# atxmega_e5_1.net
KiCad netlist of a schematic drawn in EAGLE
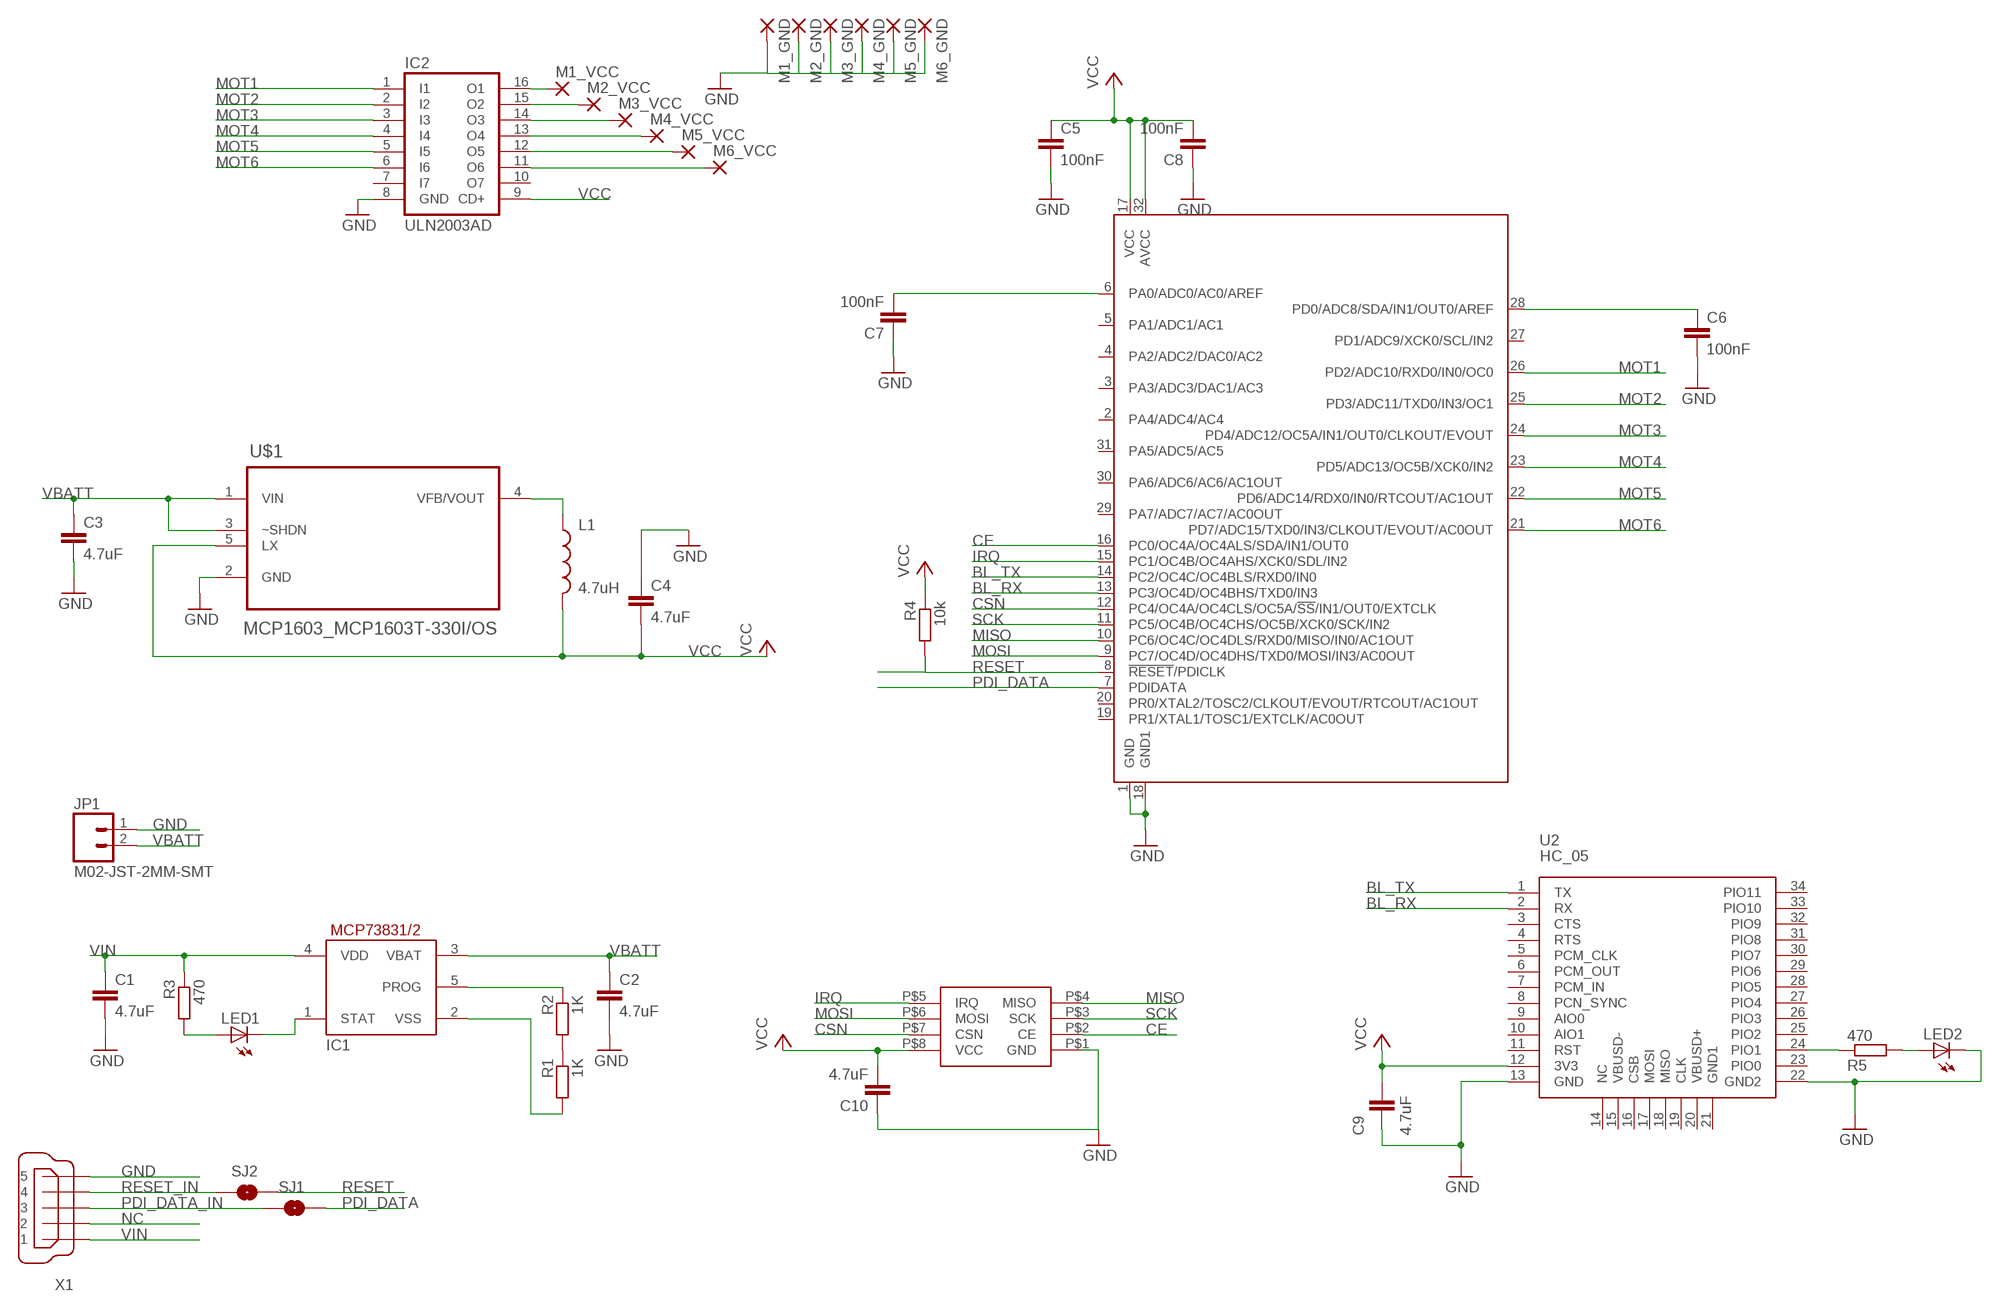
[diagram p0: schematic, sheet 1]

(export (version "E")
  (design (tool "Eeschema 10.0.6"))
  (components
    (comp (ref "C1")
      (value "4.7uF")
      (footprint "eagle-import:C0603K")
      (libsource (lib "eagle-import") (part "C-EUC0603K"))
    )
    (comp (ref "C2")
      (value "4.7uF")
      (footprint "eagle-import:C0603K")
      (libsource (lib "eagle-import") (part "C-EUC0603K"))
    )
    (comp (ref "C3")
      (value "4.7uF")
      (footprint "eagle-import:C0603K")
      (libsource (lib "eagle-import") (part "C-EUC0603K"))
    )
    (comp (ref "C4")
      (value "4.7uF")
      (footprint "eagle-import:C0603K")
      (libsource (lib "eagle-import") (part "C-EUC0603K"))
    )
    (comp (ref "C5")
      (value "100nF")
      (footprint "eagle-import:C0603K")
      (libsource (lib "eagle-import") (part "C-EUC0603K"))
    )
    (comp (ref "C6")
      (value "100nF")
      (footprint "eagle-import:C0603K")
      (libsource (lib "eagle-import") (part "C-EUC0603K"))
    )
    (comp (ref "C7")
      (value "100nF")
      (footprint "eagle-import:C0603K")
      (libsource (lib "eagle-import") (part "C-EUC0603K"))
    )
    (comp (ref "C8")
      (value "100nF")
      (footprint "eagle-import:C0603K")
      (libsource (lib "eagle-import") (part "C-EUC0603K"))
    )
    (comp (ref "C9")
      (value "4.7uF")
      (footprint "eagle-import:C0603K")
      (libsource (lib "eagle-import") (part "C-EUC0603K"))
    )
    (comp (ref "C10")
      (value "4.7uF")
      (footprint "eagle-import:C0603K")
      (libsource (lib "eagle-import") (part "C-EUC0603K"))
    )
    (comp (ref "IC1")
      (value "MCP73831/OT")
      (footprint "eagle-import:SOT23-5L")
      (libsource (lib "eagle-import") (part "MCP73831/OT"))
    )
    (comp (ref "IC2")
      (value "ULN2003AD")
      (footprint "eagle-import:SO16")
      (libsource (lib "eagle-import") (part "ULN2003AD"))
    )
    (comp (ref "JP1")
      (value "M02-JST-2MM-SMT")
      (footprint "eagle-import:JST-2-SMD")
      (libsource (lib "eagle-import") (part "M02-JST-2MM-SMT"))
    )
    (comp (ref "L1")
      (value "4.7uH")
      (footprint "eagle-import:1007")
      (libsource (lib "eagle-import") (part "INDUCTOR1007"))
    )
    (comp (ref "LED1")
      (value "LED0805LED")
      (footprint "eagle-import:0805LED")
      (libsource (lib "eagle-import") (part "LED0805LED"))
    )
    (comp (ref "LED2")
      (value "LED0805LED")
      (footprint "eagle-import:0805LED")
      (libsource (lib "eagle-import") (part "LED0805LED"))
    )
    (comp (ref "M1_GND")
      (value "WIREPAD2,15/1,0")
      (footprint "eagle-import:2,15_1,0")
      (libsource (lib "eagle-import") (part "WIREPAD2,15/1,0"))
    )
    (comp (ref "M1_VCC")
      (value "WIREPAD2,15/1,0")
      (footprint "eagle-import:2,15_1,0")
      (libsource (lib "eagle-import") (part "WIREPAD2,15/1,0"))
    )
    (comp (ref "M2_GND")
      (value "WIREPAD2,15/1,0")
      (footprint "eagle-import:2,15_1,0")
      (libsource (lib "eagle-import") (part "WIREPAD2,15/1,0"))
    )
    (comp (ref "M2_VCC")
      (value "WIREPAD2,15/1,0")
      (footprint "eagle-import:2,15_1,0")
      (libsource (lib "eagle-import") (part "WIREPAD2,15/1,0"))
    )
    (comp (ref "M3_GND")
      (value "WIREPAD2,15/1,0")
      (footprint "eagle-import:2,15_1,0")
      (libsource (lib "eagle-import") (part "WIREPAD2,15/1,0"))
    )
    (comp (ref "M3_VCC")
      (value "WIREPAD2,15/1,0")
      (footprint "eagle-import:2,15_1,0")
      (libsource (lib "eagle-import") (part "WIREPAD2,15/1,0"))
    )
    (comp (ref "M4_GND")
      (value "WIREPAD2,15/1,0")
      (footprint "eagle-import:2,15_1,0")
      (libsource (lib "eagle-import") (part "WIREPAD2,15/1,0"))
    )
    (comp (ref "M4_VCC")
      (value "WIREPAD2,15/1,0")
      (footprint "eagle-import:2,15_1,0")
      (libsource (lib "eagle-import") (part "WIREPAD2,15/1,0"))
    )
    (comp (ref "M5_GND")
      (value "WIREPAD2,15/1,0")
      (footprint "eagle-import:2,15_1,0")
      (libsource (lib "eagle-import") (part "WIREPAD2,15/1,0"))
    )
    (comp (ref "M5_VCC")
      (value "WIREPAD2,15/1,0")
      (footprint "eagle-import:2,15_1,0")
      (libsource (lib "eagle-import") (part "WIREPAD2,15/1,0"))
    )
    (comp (ref "M6_GND")
      (value "WIREPAD2,15/1,0")
      (footprint "eagle-import:2,15_1,0")
      (libsource (lib "eagle-import") (part "WIREPAD2,15/1,0"))
    )
    (comp (ref "M6_VCC")
      (value "WIREPAD2,15/1,0")
      (footprint "eagle-import:2,15_1,0")
      (libsource (lib "eagle-import") (part "WIREPAD2,15/1,0"))
    )
    (comp (ref "R1")
      (value "1K")
      (footprint "eagle-import:R0603")
      (libsource (lib "eagle-import") (part "R-EU_R0603"))
    )
    (comp (ref "R2")
      (value "1K")
      (footprint "eagle-import:R0603")
      (libsource (lib "eagle-import") (part "R-EU_R0603"))
    )
    (comp (ref "R3")
      (value "470")
      (footprint "eagle-import:R0603")
      (libsource (lib "eagle-import") (part "R-EU_R0603"))
    )
    (comp (ref "R4")
      (value "10k")
      (footprint "eagle-import:R0603")
      (libsource (lib "eagle-import") (part "R-EU_R0603"))
    )
    (comp (ref "R5")
      (value "470")
      (footprint "eagle-import:R0603")
      (libsource (lib "eagle-import") (part "R-EU_R0603"))
    )
    (comp (ref "SJ1")
      (value "SOLDERJUMPERNO")
      (footprint "eagle-import:SJ_2S-NO")
      (libsource (lib "eagle-import") (part "SOLDERJUMPERNO"))
    )
    (comp (ref "SJ2")
      (value "SOLDERJUMPERNO")
      (footprint "eagle-import:SJ_2S-NO")
      (libsource (lib "eagle-import") (part "SOLDERJUMPERNO"))
    )
    (comp (ref "U$1")
      (value "MCP1603_MCP1603T-330I/OS")
      (footprint "eagle-import:MCP1603_SOT95P280X110-5N")
      (fields (field (name "MPN") "MCP1603T-330I/OS"))
      (libsource (lib "eagle-import") (part "MCP1603_MCP1603T-330I/OS"))
    )
    (comp (ref "U$2")
      (value "NRF24L01+")
      (footprint "eagle-import:NRF24L01+")
      (libsource (lib "eagle-import") (part "NRF24L01+"))
    )
    (comp (ref "U1")
      (value "ATXMEGAE5AU")
      (footprint "eagle-import:TQFP32")
      (libsource (lib "eagle-import") (part "ATXMEGAE5AU"))
    )
    (comp (ref "U2")
      (value "HC_05")
      (footprint "eagle-import:BLUETOOTH_SMD")
      (libsource (lib "eagle-import") (part "HC_05"))
    )
    (comp (ref "X1")
      (value "MINI-USB-32005-201")
      (footprint "eagle-import:32005-201")
      (libsource (lib "eagle-import") (part "MINI-USB-32005-201"))
    )
  )
  (nets
    (net (code "1") (name "/BL_RX") (class "Default")
      (node (ref "U1") (pin "13") (pinfunction "PC3/OC4D/OC4BHS/TXD0/IN3_13") (pintype "bidirectional"))
      (node (ref "U2") (pin "2") (pinfunction "RX_2") (pintype "bidirectional"))
    )
    (net (code "2") (name "/BL_TX") (class "Default")
      (node (ref "U1") (pin "14") (pinfunction "PC2/OC4C/OC4BLS/RXD0/IN0_14") (pintype "bidirectional"))
      (node (ref "U2") (pin "1") (pinfunction "TX_1") (pintype "bidirectional"))
    )
    (net (code "3") (name "/CE") (class "Default")
      (node (ref "U$2") (pin "P$2") (pinfunction "CE_P$2") (pintype "bidirectional"))
      (node (ref "U1") (pin "16") (pinfunction "PC0/OC4A/OC4ALS/SDA/IN1/OUT0_16") (pintype "bidirectional"))
    )
    (net (code "4") (name "/CSN") (class "Default")
      (node (ref "U$2") (pin "P$7") (pinfunction "CSN_P$7") (pintype "bidirectional"))
      (node (ref "U1") (pin "12") (pinfunction "PC4/OC4A/OC4CLS/OC5A/~{SS}/IN1/OUT0/EXTCLK_12") (pintype "bidirectional"))
    )
    (net (code "5") (name "/IRQ") (class "Default")
      (node (ref "U$2") (pin "P$5") (pinfunction "IRQ_P$5") (pintype "bidirectional"))
      (node (ref "U1") (pin "15") (pinfunction "PC1/OC4B/OC4AHS/XCK0/SDL/IN2_15") (pintype "bidirectional"))
    )
    (net (code "6") (name "/MISO") (class "Default")
      (node (ref "U$2") (pin "P$4") (pinfunction "MISO_P$4") (pintype "bidirectional"))
      (node (ref "U1") (pin "10") (pinfunction "PC6/OC4C/OC4DLS/RXD0/MISO/IN0/AC1OUT_10") (pintype "bidirectional"))
    )
    (net (code "7") (name "/MOSI") (class "Default")
      (node (ref "U$2") (pin "P$6") (pinfunction "MOSI_P$6") (pintype "bidirectional"))
      (node (ref "U1") (pin "9") (pinfunction "PC7/OC4D/OC4DHS/TXD0/MOSI/IN3/AC0OUT_9") (pintype "bidirectional"))
    )
    (net (code "8") (name "/MOT1") (class "Default")
      (node (ref "IC2") (pin "1") (pinfunction "I1_1") (pintype "input"))
      (node (ref "U1") (pin "26") (pinfunction "PD2/ADC10/RXD0/IN0/OC0_26") (pintype "bidirectional"))
    )
    (net (code "9") (name "/MOT2") (class "Default")
      (node (ref "IC2") (pin "2") (pinfunction "I2_2") (pintype "input"))
      (node (ref "U1") (pin "25") (pinfunction "PD3/ADC11/TXD0/IN3/OC1_25") (pintype "bidirectional"))
    )
    (net (code "10") (name "/MOT3") (class "Default")
      (node (ref "IC2") (pin "3") (pinfunction "I3_3") (pintype "input"))
      (node (ref "U1") (pin "24") (pinfunction "PD4/ADC12/OC5A/IN1/OUT0/CLKOUT/EVOUT_24") (pintype "bidirectional"))
    )
    (net (code "11") (name "/MOT4") (class "Default")
      (node (ref "IC2") (pin "4") (pinfunction "I4_4") (pintype "input"))
      (node (ref "U1") (pin "23") (pinfunction "PD5/ADC13/OC5B/XCK0/IN2_23") (pintype "bidirectional"))
    )
    (net (code "12") (name "/MOT5") (class "Default")
      (node (ref "IC2") (pin "5") (pinfunction "I5_5") (pintype "input"))
      (node (ref "U1") (pin "22") (pinfunction "PD6/ADC14/RDX0/IN0/RTCOUT/AC1OUT_22") (pintype "bidirectional"))
    )
    (net (code "13") (name "/MOT6") (class "Default")
      (node (ref "IC2") (pin "6") (pinfunction "I6_6") (pintype "input"))
      (node (ref "U1") (pin "21") (pinfunction "PD7/ADC15/TXD0/IN3/CLKOUT/EVOUT/AC0OUT_21") (pintype "bidirectional"))
    )
    (net (code "14") (name "/NC") (class "Default")
      (node (ref "X1") (pin "2") (pinfunction "2_2") (pintype "passive"))
    )
    (net (code "15") (name "/PDI_DATA") (class "Default")
      (node (ref "SJ1") (pin "2") (pinfunction "2_2") (pintype "passive"))
      (node (ref "U1") (pin "7") (pinfunction "PDIDATA_7") (pintype "bidirectional"))
    )
    (net (code "16") (name "/PDI_DATA_IN") (class "Default")
      (node (ref "SJ1") (pin "1") (pinfunction "1_1") (pintype "passive"))
      (node (ref "X1") (pin "3") (pinfunction "3_3") (pintype "passive"))
    )
    (net (code "17") (name "/RESET") (class "Default")
      (node (ref "R4") (pin "2") (pinfunction "2_2") (pintype "passive"))
      (node (ref "SJ2") (pin "2") (pinfunction "2_2") (pintype "passive"))
      (node (ref "U1") (pin "8") (pinfunction "~{RESET}/PDICLK_8") (pintype "bidirectional"))
    )
    (net (code "18") (name "/RESET_IN") (class "Default")
      (node (ref "SJ2") (pin "1") (pinfunction "1_1") (pintype "passive"))
      (node (ref "X1") (pin "4") (pinfunction "4_4") (pintype "passive"))
    )
    (net (code "19") (name "/SCK") (class "Default")
      (node (ref "U$2") (pin "P$3") (pinfunction "SCK_P$3") (pintype "bidirectional"))
      (node (ref "U1") (pin "11") (pinfunction "PC5/OC4B/OC4CHS/OC5B/XCK0/SCK/IN2_11") (pintype "bidirectional"))
    )
    (net (code "20") (name "/VBATT") (class "Default")
      (node (ref "C2") (pin "1") (pinfunction "1_1") (pintype "passive"))
      (node (ref "C3") (pin "1") (pinfunction "1_1") (pintype "passive"))
      (node (ref "IC1") (pin "3") (pinfunction "VBAT_3") (pintype "bidirectional"))
      (node (ref "JP1") (pin "2") (pinfunction "1_2") (pintype "passive"))
      (node (ref "U$1") (pin "1") (pinfunction "VIN_1") (pintype "power_in"))
      (node (ref "U$1") (pin "3") (pinfunction "~{SHDN}_3") (pintype "input"))
    )
    (net (code "21") (name "/VIN") (class "Default")
      (node (ref "C1") (pin "1") (pinfunction "1_1") (pintype "passive"))
      (node (ref "IC1") (pin "4") (pinfunction "VDD_4") (pintype "power_in"))
      (node (ref "R3") (pin "1") (pinfunction "1_1") (pintype "passive"))
      (node (ref "X1") (pin "1") (pinfunction "1_1") (pintype "passive"))
    )
    (net (code "22") (name "GND") (class "Default")
      (node (ref "C1") (pin "2") (pinfunction "2_2") (pintype "passive"))
      (node (ref "C10") (pin "1") (pinfunction "1_1") (pintype "passive"))
      (node (ref "C2") (pin "2") (pinfunction "2_2") (pintype "passive"))
      (node (ref "C3") (pin "2") (pinfunction "2_2") (pintype "passive"))
      (node (ref "C4") (pin "1") (pinfunction "1_1") (pintype "passive"))
      (node (ref "C5") (pin "2") (pinfunction "2_2") (pintype "passive"))
      (node (ref "C6") (pin "2") (pinfunction "2_2") (pintype "passive"))
      (node (ref "C7") (pin "1") (pinfunction "1_1") (pintype "passive"))
      (node (ref "C8") (pin "1") (pinfunction "1_1") (pintype "passive"))
      (node (ref "C9") (pin "2") (pinfunction "2_2") (pintype "passive"))
      (node (ref "IC2") (pin "8") (pinfunction "GND_8") (pintype "power_in"))
      (node (ref "JP1") (pin "1") (pinfunction "2_1") (pintype "passive"))
      (node (ref "LED2") (pin "C") (pinfunction "C_C") (pintype "passive"))
      (node (ref "M1_GND") (pin "1") (pinfunction "P_1") (pintype "passive"))
      (node (ref "M2_GND") (pin "1") (pinfunction "P_1") (pintype "passive"))
      (node (ref "M3_GND") (pin "1") (pinfunction "P_1") (pintype "passive"))
      (node (ref "M4_GND") (pin "1") (pinfunction "P_1") (pintype "passive"))
      (node (ref "M5_GND") (pin "1") (pinfunction "P_1") (pintype "passive"))
      (node (ref "M6_GND") (pin "1") (pinfunction "P_1") (pintype "passive"))
      (node (ref "U$1") (pin "2") (pinfunction "GND_2") (pintype "passive"))
      (node (ref "U$2") (pin "P$1") (pinfunction "GND_P$1") (pintype "power_in"))
      (node (ref "U1") (pin "1") (pinfunction "GND_1") (pintype "bidirectional"))
      (node (ref "U1") (pin "18") (pinfunction "GND1_18") (pintype "bidirectional"))
      (node (ref "U2") (pin "13") (pinfunction "GND_13") (pintype "bidirectional"))
      (node (ref "U2") (pin "22") (pinfunction "GND2_22") (pintype "bidirectional"))
      (node (ref "X1") (pin "5") (pinfunction "5_5") (pintype "passive"))
    )
    (net (code "23") (name "Net-(IC1-PROG)") (class "Default")
      (node (ref "IC1") (pin "5") (pinfunction "PROG_5") (pintype "input"))
      (node (ref "R2") (pin "1") (pinfunction "1_1") (pintype "passive"))
    )
    (net (code "24") (name "Net-(IC1-STAT)") (class "Default")
      (node (ref "IC1") (pin "1") (pinfunction "STAT_1") (pintype "output"))
      (node (ref "LED1") (pin "C") (pinfunction "C_C") (pintype "passive"))
    )
    (net (code "25") (name "Net-(IC1-VSS)") (class "Default")
      (node (ref "IC1") (pin "2") (pinfunction "VSS_2") (pintype "power_in"))
      (node (ref "R1") (pin "2") (pinfunction "2_2") (pintype "passive"))
    )
    (net (code "26") (name "Net-(IC2-O1)") (class "Default")
      (node (ref "IC2") (pin "16") (pinfunction "O1_16") (pintype "open_collector"))
      (node (ref "M1_VCC") (pin "1") (pinfunction "P_1") (pintype "passive"))
    )
    (net (code "27") (name "Net-(IC2-O2)") (class "Default")
      (node (ref "IC2") (pin "15") (pinfunction "O2_15") (pintype "open_collector"))
      (node (ref "M2_VCC") (pin "1") (pinfunction "P_1") (pintype "passive"))
    )
    (net (code "28") (name "Net-(IC2-O3)") (class "Default")
      (node (ref "IC2") (pin "14") (pinfunction "O3_14") (pintype "open_collector"))
      (node (ref "M3_VCC") (pin "1") (pinfunction "P_1") (pintype "passive"))
    )
    (net (code "29") (name "Net-(IC2-O4)") (class "Default")
      (node (ref "IC2") (pin "13") (pinfunction "O4_13") (pintype "open_collector"))
      (node (ref "M4_VCC") (pin "1") (pinfunction "P_1") (pintype "passive"))
    )
    (net (code "30") (name "Net-(IC2-O5)") (class "Default")
      (node (ref "IC2") (pin "12") (pinfunction "O5_12") (pintype "open_collector"))
      (node (ref "M5_VCC") (pin "1") (pinfunction "P_1") (pintype "passive"))
    )
    (net (code "31") (name "Net-(IC2-O6)") (class "Default")
      (node (ref "IC2") (pin "11") (pinfunction "O6_11") (pintype "open_collector"))
      (node (ref "M6_VCC") (pin "1") (pinfunction "P_1") (pintype "passive"))
    )
    (net (code "32") (name "Net-(LED1-PadA)") (class "Default")
      (node (ref "LED1") (pin "A") (pinfunction "A_A") (pintype "passive"))
      (node (ref "R3") (pin "2") (pinfunction "2_2") (pintype "passive"))
    )
    (net (code "33") (name "Net-(LED2-PadA)") (class "Default")
      (node (ref "LED2") (pin "A") (pinfunction "A_A") (pintype "passive"))
      (node (ref "R5") (pin "2") (pinfunction "2_2") (pintype "passive"))
    )
    (net (code "34") (name "Net-(R1-Pad1)") (class "Default")
      (node (ref "R1") (pin "1") (pinfunction "1_1") (pintype "passive"))
      (node (ref "R2") (pin "2") (pinfunction "2_2") (pintype "passive"))
    )
    (net (code "35") (name "Net-(U$1-VFB{slash}VOUT)") (class "Default")
      (node (ref "L1") (pin "1") (pinfunction "1_1") (pintype "passive"))
      (node (ref "U$1") (pin "4") (pinfunction "VFB/VOUT_4") (pintype "output"))
    )
    (net (code "36") (name "Net-(U1-PA0{slash}ADC0{slash}AC0{slash}AREF)") (class "Default")
      (node (ref "C7") (pin "2") (pinfunction "2_2") (pintype "passive"))
      (node (ref "U1") (pin "6") (pinfunction "PA0/ADC0/AC0/AREF_6") (pintype "bidirectional"))
    )
    (net (code "37") (name "Net-(U1-PD0{slash}ADC8{slash}SDA{slash}IN1{slash}OUT0{slash}AREF)") (class "Default")
      (node (ref "C6") (pin "1") (pinfunction "1_1") (pintype "passive"))
      (node (ref "U1") (pin "28") (pinfunction "PD0/ADC8/SDA/IN1/OUT0/AREF_28") (pintype "bidirectional"))
    )
    (net (code "38") (name "Net-(U2-PIO1)") (class "Default")
      (node (ref "R5") (pin "1") (pinfunction "1_1") (pintype "passive"))
      (node (ref "U2") (pin "24") (pinfunction "PIO1_24") (pintype "bidirectional"))
    )
    (net (code "39") (name "VCC") (class "Default")
      (node (ref "C10") (pin "2") (pinfunction "2_2") (pintype "passive"))
      (node (ref "C4") (pin "2") (pinfunction "2_2") (pintype "passive"))
      (node (ref "C5") (pin "1") (pinfunction "1_1") (pintype "passive"))
      (node (ref "C8") (pin "2") (pinfunction "2_2") (pintype "passive"))
      (node (ref "C9") (pin "1") (pinfunction "1_1") (pintype "passive"))
      (node (ref "IC2") (pin "9") (pinfunction "CD+_9") (pintype "passive"))
      (node (ref "L1") (pin "2") (pinfunction "2_2") (pintype "passive"))
      (node (ref "R4") (pin "1") (pinfunction "1_1") (pintype "passive"))
      (node (ref "U$1") (pin "5") (pinfunction "LX_5") (pintype "input"))
      (node (ref "U$2") (pin "P$8") (pinfunction "VCC_P$8") (pintype "power_in"))
      (node (ref "U1") (pin "17") (pinfunction "VCC_17") (pintype "bidirectional"))
      (node (ref "U1") (pin "32") (pinfunction "AVCC_32") (pintype "bidirectional"))
      (node (ref "U2") (pin "12") (pinfunction "3V3_12") (pintype "bidirectional"))
    )
    (net (code "40") (name "unconnected-(IC2-I7-Pad7)") (class "Default")
      (node (ref "IC2") (pin "7") (pinfunction "I7_7") (pintype "input"))
    )
    (net (code "41") (name "unconnected-(IC2-O7-Pad10)") (class "Default")
      (node (ref "IC2") (pin "10") (pinfunction "O7_10") (pintype "open_collector"))
    )
    (net (code "42") (name "unconnected-(U1-PA1{slash}ADC1{slash}AC1-Pad5)") (class "Default")
      (node (ref "U1") (pin "5") (pinfunction "PA1/ADC1/AC1_5") (pintype "bidirectional"))
    )
    (net (code "43") (name "unconnected-(U1-PA2{slash}ADC2{slash}DAC0{slash}AC2-Pad4)") (class "Default")
      (node (ref "U1") (pin "4") (pinfunction "PA2/ADC2/DAC0/AC2_4") (pintype "bidirectional"))
    )
    (net (code "44") (name "unconnected-(U1-PA3{slash}ADC3{slash}DAC1{slash}AC3-Pad3)") (class "Default")
      (node (ref "U1") (pin "3") (pinfunction "PA3/ADC3/DAC1/AC3_3") (pintype "bidirectional"))
    )
    (net (code "45") (name "unconnected-(U1-PA4{slash}ADC4{slash}AC4-Pad2)") (class "Default")
      (node (ref "U1") (pin "2") (pinfunction "PA4/ADC4/AC4_2") (pintype "bidirectional"))
    )
    (net (code "46") (name "unconnected-(U1-PA5{slash}ADC5{slash}AC5-Pad31)") (class "Default")
      (node (ref "U1") (pin "31") (pinfunction "PA5/ADC5/AC5_31") (pintype "bidirectional"))
    )
    (net (code "47") (name "unconnected-(U1-PA6{slash}ADC6{slash}AC6{slash}AC1OUT-Pad30)") (class "Default")
      (node (ref "U1") (pin "30") (pinfunction "PA6/ADC6/AC6/AC1OUT_30") (pintype "bidirectional"))
    )
    (net (code "48") (name "unconnected-(U1-PA7{slash}ADC7{slash}AC7{slash}AC0OUT-Pad29)") (class "Default")
      (node (ref "U1") (pin "29") (pinfunction "PA7/ADC7/AC7/AC0OUT_29") (pintype "bidirectional"))
    )
    (net (code "49") (name "unconnected-(U1-PD1{slash}ADC9{slash}XCK0{slash}SCL{slash}IN2-Pad27)") (class "Default")
      (node (ref "U1") (pin "27") (pinfunction "PD1/ADC9/XCK0/SCL/IN2_27") (pintype "bidirectional"))
    )
    (net (code "50") (name "unconnected-(U1-PR0{slash}XTAL2{slash}TOSC2{slash}CLKOUT{slash}EVOUT{slash}RTCOUT{slash}AC1OUT-Pad20)") (class "Default")
      (node (ref "U1") (pin "20") (pinfunction "PR0/XTAL2/TOSC2/CLKOUT/EVOUT/RTCOUT/AC1OUT_20") (pintype "bidirectional"))
    )
    (net (code "51") (name "unconnected-(U1-PR1{slash}XTAL1{slash}TOSC1{slash}EXTCLK{slash}AC0OUT-Pad19)") (class "Default")
      (node (ref "U1") (pin "19") (pinfunction "PR1/XTAL1/TOSC1/EXTCLK/AC0OUT_19") (pintype "bidirectional"))
    )
    (net (code "52") (name "unconnected-(U2-AIO0-Pad9)") (class "Default")
      (node (ref "U2") (pin "9") (pinfunction "AIO0_9") (pintype "bidirectional"))
    )
    (net (code "53") (name "unconnected-(U2-AIO1-Pad10)") (class "Default")
      (node (ref "U2") (pin "10") (pinfunction "AIO1_10") (pintype "bidirectional"))
    )
    (net (code "54") (name "unconnected-(U2-CLK-Pad19)") (class "Default")
      (node (ref "U2") (pin "19") (pinfunction "CLK_19") (pintype "bidirectional"))
    )
    (net (code "55") (name "unconnected-(U2-CSB-Pad16)") (class "Default")
      (node (ref "U2") (pin "16") (pinfunction "CSB_16") (pintype "bidirectional"))
    )
    (net (code "56") (name "unconnected-(U2-CTS-Pad3)") (class "Default")
      (node (ref "U2") (pin "3") (pinfunction "CTS_3") (pintype "bidirectional"))
    )
    (net (code "57") (name "unconnected-(U2-GND1-Pad21)") (class "Default")
      (node (ref "U2") (pin "21") (pinfunction "GND1_21") (pintype "bidirectional"))
    )
    (net (code "58") (name "unconnected-(U2-MISO-Pad18)") (class "Default")
      (node (ref "U2") (pin "18") (pinfunction "MISO_18") (pintype "bidirectional"))
    )
    (net (code "59") (name "unconnected-(U2-MOSI-Pad17)") (class "Default")
      (node (ref "U2") (pin "17") (pinfunction "MOSI_17") (pintype "bidirectional"))
    )
    (net (code "60") (name "unconnected-(U2-NC-Pad14)") (class "Default")
      (node (ref "U2") (pin "14") (pinfunction "NC_14") (pintype "bidirectional"))
    )
    (net (code "61") (name "unconnected-(U2-PCM_CLK-Pad5)") (class "Default")
      (node (ref "U2") (pin "5") (pinfunction "PCM_CLK_5") (pintype "bidirectional"))
    )
    (net (code "62") (name "unconnected-(U2-PCM_IN-Pad7)") (class "Default")
      (node (ref "U2") (pin "7") (pinfunction "PCM_IN_7") (pintype "bidirectional"))
    )
    (net (code "63") (name "unconnected-(U2-PCM_OUT-Pad6)") (class "Default")
      (node (ref "U2") (pin "6") (pinfunction "PCM_OUT_6") (pintype "bidirectional"))
    )
    (net (code "64") (name "unconnected-(U2-PCN_SYNC-Pad8)") (class "Default")
      (node (ref "U2") (pin "8") (pinfunction "PCN_SYNC_8") (pintype "bidirectional"))
    )
    (net (code "65") (name "unconnected-(U2-PIO0-Pad23)") (class "Default")
      (node (ref "U2") (pin "23") (pinfunction "PIO0_23") (pintype "bidirectional"))
    )
    (net (code "66") (name "unconnected-(U2-PIO2-Pad25)") (class "Default")
      (node (ref "U2") (pin "25") (pinfunction "PIO2_25") (pintype "bidirectional"))
    )
    (net (code "67") (name "unconnected-(U2-PIO3-Pad26)") (class "Default")
      (node (ref "U2") (pin "26") (pinfunction "PIO3_26") (pintype "bidirectional"))
    )
    (net (code "68") (name "unconnected-(U2-PIO4-Pad27)") (class "Default")
      (node (ref "U2") (pin "27") (pinfunction "PIO4_27") (pintype "bidirectional"))
    )
    (net (code "69") (name "unconnected-(U2-PIO5-Pad28)") (class "Default")
      (node (ref "U2") (pin "28") (pinfunction "PIO5_28") (pintype "bidirectional"))
    )
    (net (code "70") (name "unconnected-(U2-PIO6-Pad29)") (class "Default")
      (node (ref "U2") (pin "29") (pinfunction "PIO6_29") (pintype "bidirectional"))
    )
    (net (code "71") (name "unconnected-(U2-PIO7-Pad30)") (class "Default")
      (node (ref "U2") (pin "30") (pinfunction "PIO7_30") (pintype "bidirectional"))
    )
    (net (code "72") (name "unconnected-(U2-PIO8-Pad31)") (class "Default")
      (node (ref "U2") (pin "31") (pinfunction "PIO8_31") (pintype "bidirectional"))
    )
    (net (code "73") (name "unconnected-(U2-PIO9-Pad32)") (class "Default")
      (node (ref "U2") (pin "32") (pinfunction "PIO9_32") (pintype "bidirectional"))
    )
    (net (code "74") (name "unconnected-(U2-PIO10-Pad33)") (class "Default")
      (node (ref "U2") (pin "33") (pinfunction "PIO10_33") (pintype "bidirectional"))
    )
    (net (code "75") (name "unconnected-(U2-PIO11-Pad34)") (class "Default")
      (node (ref "U2") (pin "34") (pinfunction "PIO11_34") (pintype "bidirectional"))
    )
    (net (code "76") (name "unconnected-(U2-RST-Pad11)") (class "Default")
      (node (ref "U2") (pin "11") (pinfunction "RST_11") (pintype "bidirectional"))
    )
    (net (code "77") (name "unconnected-(U2-RTS-Pad4)") (class "Default")
      (node (ref "U2") (pin "4") (pinfunction "RTS_4") (pintype "bidirectional"))
    )
    (net (code "78") (name "unconnected-(U2-VBUSD+-Pad20)") (class "Default")
      (node (ref "U2") (pin "20") (pinfunction "VBUSD+_20") (pintype "bidirectional"))
    )
    (net (code "79") (name "unconnected-(U2-VBUSD--Pad15)") (class "Default")
      (node (ref "U2") (pin "15") (pinfunction "VBUSD-_15") (pintype "bidirectional"))
    )
  )
)
